# DA_uno_shield_1_0.net
KiCad netlist of a schematic drawn in EAGLE
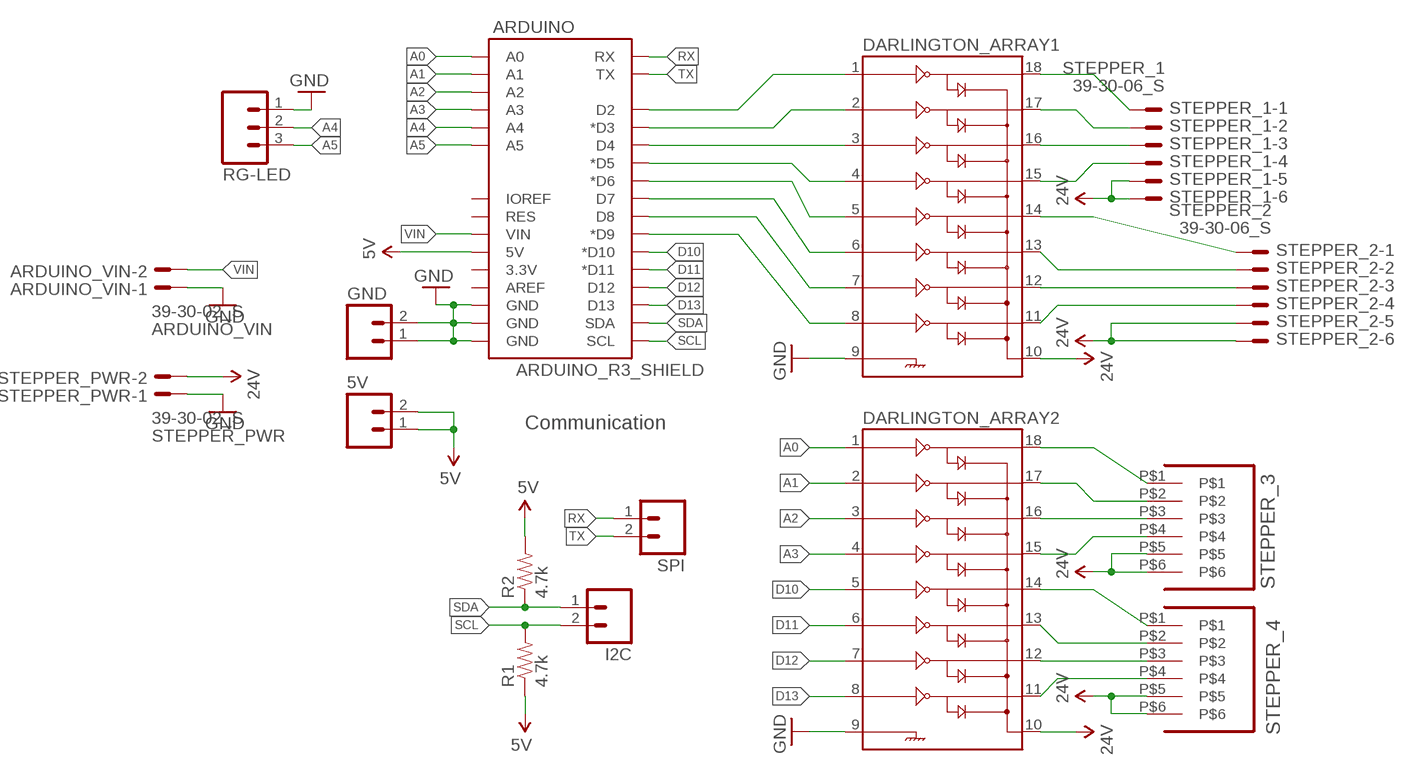
[diagram p0: schematic, sheet 1]

(export (version "E")
  (design (tool "Eeschema 10.0.6"))
  (components
    (comp (ref "5V")
      (value "M021X02_NO_SILK")
      (footprint "eagle-import:1X02_NO_SILK")
      (libsource (lib "eagle-import") (part "M021X02_NO_SILK"))
    )
    (comp (ref "ARDUINO")
      (value "ARDUINO_R3_SHIELD")
      (footprint "eagle-import:UNO_R3_SHIELD")
      (libsource (lib "eagle-import") (part "ARDUINO_R3_SHIELD"))
    )
    (comp (ref "ARDUINO_VIN")
      (value "39-30-02_S")
      (footprint "eagle-import:39-30-_02_")
      (libsource (lib "eagle-import") (part "39-30-?02?_S"))
    )
    (comp (ref "DARLINGTON_ARRAY1")
      (value "ULN2803DIP")
      (footprint "eagle-import:DIL18")
      (libsource (lib "eagle-import") (part "ULN2803DIP"))
    )
    (comp (ref "DARLINGTON_ARRAY2")
      (value "ULN2803DIP")
      (footprint "eagle-import:DIL18")
      (libsource (lib "eagle-import") (part "ULN2803DIP"))
    )
    (comp (ref "GND")
      (value "M021X02_NO_SILK")
      (footprint "eagle-import:1X02_NO_SILK")
      (libsource (lib "eagle-import") (part "M021X02_NO_SILK"))
    )
    (comp (ref "I2C")
      (value "M021X02_NO_SILK")
      (footprint "eagle-import:1X02_NO_SILK")
      (libsource (lib "eagle-import") (part "M021X02_NO_SILK"))
    )
    (comp (ref "R1")
      (value "4.7k")
      (footprint "eagle-import:AXIAL-0.3-KIT")
      (libsource (lib "eagle-import") (part "RESISTORKIT"))
    )
    (comp (ref "R2")
      (value "4.7k")
      (footprint "eagle-import:AXIAL-0.3-KIT")
      (libsource (lib "eagle-import") (part "RESISTORKIT"))
    )
    (comp (ref "RG-LED")
      (value "M03LOCK_NO_SILK")
      (footprint "eagle-import:1X03_LOCK_NO_SILK")
      (libsource (lib "eagle-import") (part "M03LOCK_NO_SILK"))
    )
    (comp (ref "SPI")
      (value "M021X02_NO_SILK")
      (footprint "eagle-import:1X02_NO_SILK")
      (libsource (lib "eagle-import") (part "M021X02_NO_SILK"))
    )
    (comp (ref "STEPPER_1")
      (value "39-30-06_S")
      (footprint "eagle-import:39-30-_06_")
      (libsource (lib "eagle-import") (part "39-30-?06?_S"))
    )
    (comp (ref "STEPPER_2")
      (value "39-30-06_S")
      (footprint "eagle-import:39-30-_06_")
      (libsource (lib "eagle-import") (part "39-30-?06?_S"))
    )
    (comp (ref "STEPPER_3")
      (value "39-29-06")
      (footprint "eagle-import:39-29-_06_")
      (libsource (lib "eagle-import") (part "39-29-?06?"))
    )
    (comp (ref "STEPPER_4")
      (value "39-29-06")
      (footprint "eagle-import:39-29-_06_")
      (libsource (lib "eagle-import") (part "39-29-?06?"))
    )
    (comp (ref "STEPPER_PWR")
      (value "39-30-02_S")
      (footprint "eagle-import:39-30-_02_")
      (libsource (lib "eagle-import") (part "39-30-?02?_S"))
    )
  )
  (nets
    (net (code "1") (name "5V") (class "Default")
      (node (ref "5V") (pin "1") (pinfunction "1_1") (pintype "passive"))
      (node (ref "5V") (pin "2") (pinfunction "2_2") (pintype "passive"))
      (node (ref "ARDUINO") (pin "5V") (pinfunction "5V_5V") (pintype "bidirectional"))
      (node (ref "R1") (pin "P$1") (pinfunction "1_P$1") (pintype "passive"))
      (node (ref "R2") (pin "P$2") (pinfunction "2_P$2") (pintype "passive"))
    )
    (net (code "2") (name "24V") (class "Default")
      (node (ref "DARLINGTON_ARRAY1") (pin "10") (pinfunction "10_10") (pintype "bidirectional"))
      (node (ref "DARLINGTON_ARRAY2") (pin "10") (pinfunction "10_10") (pintype "bidirectional"))
      (node (ref "STEPPER_1") (pin "5") (pinfunction "P_5") (pintype "passive"))
      (node (ref "STEPPER_1") (pin "6") (pinfunction "P_6") (pintype "passive"))
      (node (ref "STEPPER_2") (pin "5") (pinfunction "P_5") (pintype "passive"))
      (node (ref "STEPPER_2") (pin "6") (pinfunction "P_6") (pintype "passive"))
      (node (ref "STEPPER_3") (pin "P$5") (pinfunction "P$5_P$5") (pintype "bidirectional"))
      (node (ref "STEPPER_3") (pin "P$6") (pinfunction "P$6_P$6") (pintype "bidirectional"))
      (node (ref "STEPPER_4") (pin "P$5") (pinfunction "P$5_P$5") (pintype "bidirectional"))
      (node (ref "STEPPER_4") (pin "P$6") (pinfunction "P$6_P$6") (pintype "bidirectional"))
      (node (ref "STEPPER_PWR") (pin "2") (pinfunction "P_2") (pintype "passive"))
    )
    (net (code "3") (name "A0") (class "Default")
      (node (ref "ARDUINO") (pin "A0") (pinfunction "A0_A0") (pintype "bidirectional"))
      (node (ref "DARLINGTON_ARRAY2") (pin "1") (pinfunction "1_1") (pintype "bidirectional"))
    )
    (net (code "4") (name "A1") (class "Default")
      (node (ref "ARDUINO") (pin "A1") (pinfunction "A1_A1") (pintype "bidirectional"))
      (node (ref "DARLINGTON_ARRAY2") (pin "2") (pinfunction "2_2") (pintype "bidirectional"))
    )
    (net (code "5") (name "A2") (class "Default")
      (node (ref "ARDUINO") (pin "A2") (pinfunction "A2_A2") (pintype "bidirectional"))
      (node (ref "DARLINGTON_ARRAY2") (pin "3") (pinfunction "3_3") (pintype "bidirectional"))
    )
    (net (code "6") (name "A3") (class "Default")
      (node (ref "ARDUINO") (pin "A3") (pinfunction "A3_A3") (pintype "bidirectional"))
      (node (ref "DARLINGTON_ARRAY2") (pin "4") (pinfunction "4_4") (pintype "bidirectional"))
    )
    (net (code "7") (name "A4") (class "Default")
      (node (ref "ARDUINO") (pin "A4") (pinfunction "A4_A4") (pintype "bidirectional"))
      (node (ref "RG-LED") (pin "2") (pinfunction "2_2") (pintype "passive"))
    )
    (net (code "8") (name "A5") (class "Default")
      (node (ref "ARDUINO") (pin "A5") (pinfunction "A5_A5") (pintype "bidirectional"))
      (node (ref "RG-LED") (pin "3") (pinfunction "3_3") (pintype "passive"))
    )
    (net (code "9") (name "D10") (class "Default")
      (node (ref "ARDUINO") (pin "D10") (pinfunction "*D10_D10") (pintype "bidirectional"))
      (node (ref "DARLINGTON_ARRAY2") (pin "5") (pinfunction "5_5") (pintype "bidirectional"))
    )
    (net (code "10") (name "D11") (class "Default")
      (node (ref "ARDUINO") (pin "D11") (pinfunction "*D11_D11") (pintype "bidirectional"))
      (node (ref "DARLINGTON_ARRAY2") (pin "6") (pinfunction "6_6") (pintype "bidirectional"))
    )
    (net (code "11") (name "D12") (class "Default")
      (node (ref "ARDUINO") (pin "D12") (pinfunction "D12_D12") (pintype "bidirectional"))
      (node (ref "DARLINGTON_ARRAY2") (pin "7") (pinfunction "7_7") (pintype "bidirectional"))
    )
    (net (code "12") (name "D13") (class "Default")
      (node (ref "ARDUINO") (pin "D13") (pinfunction "D13_D13") (pintype "bidirectional"))
      (node (ref "DARLINGTON_ARRAY2") (pin "8") (pinfunction "8_8") (pintype "bidirectional"))
    )
    (net (code "13") (name "GND") (class "Default")
      (node (ref "ARDUINO") (pin "GND@0") (pinfunction "GND_GND@0") (pintype "bidirectional"))
      (node (ref "ARDUINO") (pin "GND@1") (pinfunction "GND_GND@1") (pintype "bidirectional"))
      (node (ref "ARDUINO") (pin "GND@2") (pinfunction "GND_GND@2") (pintype "bidirectional"))
      (node (ref "ARDUINO_VIN") (pin "1") (pinfunction "P_1") (pintype "passive"))
      (node (ref "DARLINGTON_ARRAY1") (pin "9") (pinfunction "9_9") (pintype "bidirectional"))
      (node (ref "DARLINGTON_ARRAY2") (pin "9") (pinfunction "9_9") (pintype "bidirectional"))
      (node (ref "GND") (pin "1") (pinfunction "1_1") (pintype "passive"))
      (node (ref "GND") (pin "2") (pinfunction "2_2") (pintype "passive"))
      (node (ref "RG-LED") (pin "1") (pinfunction "1_1") (pintype "passive"))
      (node (ref "STEPPER_PWR") (pin "1") (pinfunction "P_1") (pintype "passive"))
    )
    (net (code "14") (name "Net-(ARDUINO-*D3)") (class "Default")
      (node (ref "ARDUINO") (pin "D3") (pinfunction "*D3_D3") (pintype "bidirectional"))
      (node (ref "DARLINGTON_ARRAY1") (pin "2") (pinfunction "2_2") (pintype "bidirectional"))
    )
    (net (code "15") (name "Net-(ARDUINO-*D5)") (class "Default")
      (node (ref "ARDUINO") (pin "D5") (pinfunction "*D5_D5") (pintype "bidirectional"))
      (node (ref "DARLINGTON_ARRAY1") (pin "4") (pinfunction "4_4") (pintype "bidirectional"))
    )
    (net (code "16") (name "Net-(ARDUINO-*D6)") (class "Default")
      (node (ref "ARDUINO") (pin "D6") (pinfunction "*D6_D6") (pintype "bidirectional"))
      (node (ref "DARLINGTON_ARRAY1") (pin "5") (pinfunction "5_5") (pintype "bidirectional"))
    )
    (net (code "17") (name "Net-(ARDUINO-*D9)") (class "Default")
      (node (ref "ARDUINO") (pin "D9") (pinfunction "*D9_D9") (pintype "bidirectional"))
      (node (ref "DARLINGTON_ARRAY1") (pin "8") (pinfunction "8_8") (pintype "bidirectional"))
    )
    (net (code "18") (name "Net-(ARDUINO-PadD2)") (class "Default")
      (node (ref "ARDUINO") (pin "D2") (pinfunction "D2_D2") (pintype "bidirectional"))
      (node (ref "DARLINGTON_ARRAY1") (pin "1") (pinfunction "1_1") (pintype "bidirectional"))
    )
    (net (code "19") (name "Net-(ARDUINO-PadD4)") (class "Default")
      (node (ref "ARDUINO") (pin "D4") (pinfunction "D4_D4") (pintype "bidirectional"))
      (node (ref "DARLINGTON_ARRAY1") (pin "3") (pinfunction "3_3") (pintype "bidirectional"))
    )
    (net (code "20") (name "Net-(ARDUINO-PadD7)") (class "Default")
      (node (ref "ARDUINO") (pin "D7") (pinfunction "D7_D7") (pintype "bidirectional"))
      (node (ref "DARLINGTON_ARRAY1") (pin "6") (pinfunction "6_6") (pintype "bidirectional"))
    )
    (net (code "21") (name "Net-(ARDUINO-PadD8)") (class "Default")
      (node (ref "ARDUINO") (pin "D8") (pinfunction "D8_D8") (pintype "bidirectional"))
      (node (ref "DARLINGTON_ARRAY1") (pin "7") (pinfunction "7_7") (pintype "bidirectional"))
    )
    (net (code "22") (name "Net-(DARLINGTON_ARRAY2-Pad11)") (class "Default")
      (node (ref "DARLINGTON_ARRAY2") (pin "11") (pinfunction "11_11") (pintype "bidirectional"))
      (node (ref "STEPPER_4") (pin "P$4") (pinfunction "P$4_P$4") (pintype "bidirectional"))
    )
    (net (code "23") (name "Net-(DARLINGTON_ARRAY2-Pad12)") (class "Default")
      (node (ref "DARLINGTON_ARRAY2") (pin "12") (pinfunction "12_12") (pintype "bidirectional"))
      (node (ref "STEPPER_4") (pin "P$3") (pinfunction "P$3_P$3") (pintype "bidirectional"))
    )
    (net (code "24") (name "Net-(DARLINGTON_ARRAY2-Pad13)") (class "Default")
      (node (ref "DARLINGTON_ARRAY2") (pin "13") (pinfunction "13_13") (pintype "bidirectional"))
      (node (ref "STEPPER_4") (pin "P$2") (pinfunction "P$2_P$2") (pintype "bidirectional"))
    )
    (net (code "25") (name "Net-(DARLINGTON_ARRAY2-Pad14)") (class "Default")
      (node (ref "DARLINGTON_ARRAY2") (pin "14") (pinfunction "14_14") (pintype "bidirectional"))
      (node (ref "STEPPER_4") (pin "P$1") (pinfunction "P$1_P$1") (pintype "bidirectional"))
    )
    (net (code "26") (name "Net-(DARLINGTON_ARRAY2-Pad15)") (class "Default")
      (node (ref "DARLINGTON_ARRAY2") (pin "15") (pinfunction "15_15") (pintype "bidirectional"))
      (node (ref "STEPPER_3") (pin "P$4") (pinfunction "P$4_P$4") (pintype "bidirectional"))
    )
    (net (code "27") (name "Net-(DARLINGTON_ARRAY2-Pad16)") (class "Default")
      (node (ref "DARLINGTON_ARRAY2") (pin "16") (pinfunction "16_16") (pintype "bidirectional"))
      (node (ref "STEPPER_3") (pin "P$3") (pinfunction "P$3_P$3") (pintype "bidirectional"))
    )
    (net (code "28") (name "Net-(DARLINGTON_ARRAY2-Pad17)") (class "Default")
      (node (ref "DARLINGTON_ARRAY2") (pin "17") (pinfunction "17_17") (pintype "bidirectional"))
      (node (ref "STEPPER_3") (pin "P$2") (pinfunction "P$2_P$2") (pintype "bidirectional"))
    )
    (net (code "29") (name "Net-(DARLINGTON_ARRAY2-Pad18)") (class "Default")
      (node (ref "DARLINGTON_ARRAY2") (pin "18") (pinfunction "18_18") (pintype "bidirectional"))
      (node (ref "STEPPER_3") (pin "P$1") (pinfunction "P$1_P$1") (pintype "bidirectional"))
    )
    (net (code "30") (name "Net-(STEPPER_1A-P)") (class "Default")
      (node (ref "DARLINGTON_ARRAY1") (pin "18") (pinfunction "18_18") (pintype "bidirectional"))
      (node (ref "STEPPER_1") (pin "1") (pinfunction "P_1") (pintype "passive"))
    )
    (net (code "31") (name "Net-(STEPPER_1B-P)") (class "Default")
      (node (ref "DARLINGTON_ARRAY1") (pin "17") (pinfunction "17_17") (pintype "bidirectional"))
      (node (ref "STEPPER_1") (pin "2") (pinfunction "P_2") (pintype "passive"))
    )
    (net (code "32") (name "Net-(STEPPER_1C-P)") (class "Default")
      (node (ref "DARLINGTON_ARRAY1") (pin "16") (pinfunction "16_16") (pintype "bidirectional"))
      (node (ref "STEPPER_1") (pin "3") (pinfunction "P_3") (pintype "passive"))
    )
    (net (code "33") (name "Net-(STEPPER_1D-P)") (class "Default")
      (node (ref "DARLINGTON_ARRAY1") (pin "15") (pinfunction "15_15") (pintype "bidirectional"))
      (node (ref "STEPPER_1") (pin "4") (pinfunction "P_4") (pintype "passive"))
    )
    (net (code "34") (name "Net-(STEPPER_2A-P)") (class "Default")
      (node (ref "DARLINGTON_ARRAY1") (pin "14") (pinfunction "14_14") (pintype "bidirectional"))
      (node (ref "STEPPER_2") (pin "1") (pinfunction "P_1") (pintype "passive"))
    )
    (net (code "35") (name "Net-(STEPPER_2B-P)") (class "Default")
      (node (ref "DARLINGTON_ARRAY1") (pin "13") (pinfunction "13_13") (pintype "bidirectional"))
      (node (ref "STEPPER_2") (pin "2") (pinfunction "P_2") (pintype "passive"))
    )
    (net (code "36") (name "Net-(STEPPER_2C-P)") (class "Default")
      (node (ref "DARLINGTON_ARRAY1") (pin "12") (pinfunction "12_12") (pintype "bidirectional"))
      (node (ref "STEPPER_2") (pin "3") (pinfunction "P_3") (pintype "passive"))
    )
    (net (code "37") (name "Net-(STEPPER_2D-P)") (class "Default")
      (node (ref "DARLINGTON_ARRAY1") (pin "11") (pinfunction "11_11") (pintype "bidirectional"))
      (node (ref "STEPPER_2") (pin "4") (pinfunction "P_4") (pintype "passive"))
    )
    (net (code "38") (name "RX") (class "Default")
      (node (ref "ARDUINO") (pin "RX") (pinfunction "RX_RX") (pintype "bidirectional"))
      (node (ref "SPI") (pin "1") (pinfunction "1_1") (pintype "passive"))
    )
    (net (code "39") (name "SCL") (class "Default")
      (node (ref "ARDUINO") (pin "SCL") (pinfunction "SCL_SCL") (pintype "bidirectional"))
      (node (ref "I2C") (pin "2") (pinfunction "2_2") (pintype "passive"))
      (node (ref "R1") (pin "P$2") (pinfunction "2_P$2") (pintype "passive"))
    )
    (net (code "40") (name "SDA") (class "Default")
      (node (ref "ARDUINO") (pin "SDA") (pinfunction "SDA_SDA") (pintype "bidirectional"))
      (node (ref "I2C") (pin "1") (pinfunction "1_1") (pintype "passive"))
      (node (ref "R2") (pin "P$1") (pinfunction "1_P$1") (pintype "passive"))
    )
    (net (code "41") (name "TX") (class "Default")
      (node (ref "ARDUINO") (pin "TX") (pinfunction "TX_TX") (pintype "bidirectional"))
      (node (ref "SPI") (pin "2") (pinfunction "2_2") (pintype "passive"))
    )
    (net (code "42") (name "VIN") (class "Default")
      (node (ref "ARDUINO") (pin "VIN") (pinfunction "VIN_VIN") (pintype "bidirectional"))
      (node (ref "ARDUINO_VIN") (pin "2") (pinfunction "P_2") (pintype "passive"))
    )
    (net (code "43") (name "unconnected-(ARDUINO-Pad3.3V)") (class "Default")
      (node (ref "ARDUINO") (pin "3.3V") (pinfunction "3.3V_3.3V") (pintype "bidirectional"))
    )
    (net (code "44") (name "unconnected-(ARDUINO-PadAREF)") (class "Default")
      (node (ref "ARDUINO") (pin "AREF") (pinfunction "AREF_AREF") (pintype "bidirectional"))
    )
    (net (code "45") (name "unconnected-(ARDUINO-PadIOREF)") (class "Default")
      (node (ref "ARDUINO") (pin "IOREF") (pinfunction "IOREF_IOREF") (pintype "bidirectional"))
    )
    (net (code "46") (name "unconnected-(ARDUINO-PadRES)") (class "Default")
      (node (ref "ARDUINO") (pin "RES") (pinfunction "RES_RES") (pintype "bidirectional"))
    )
  )
)
